# Modular_BO.net
KiCad netlist of a schematic drawn in Altium Designer
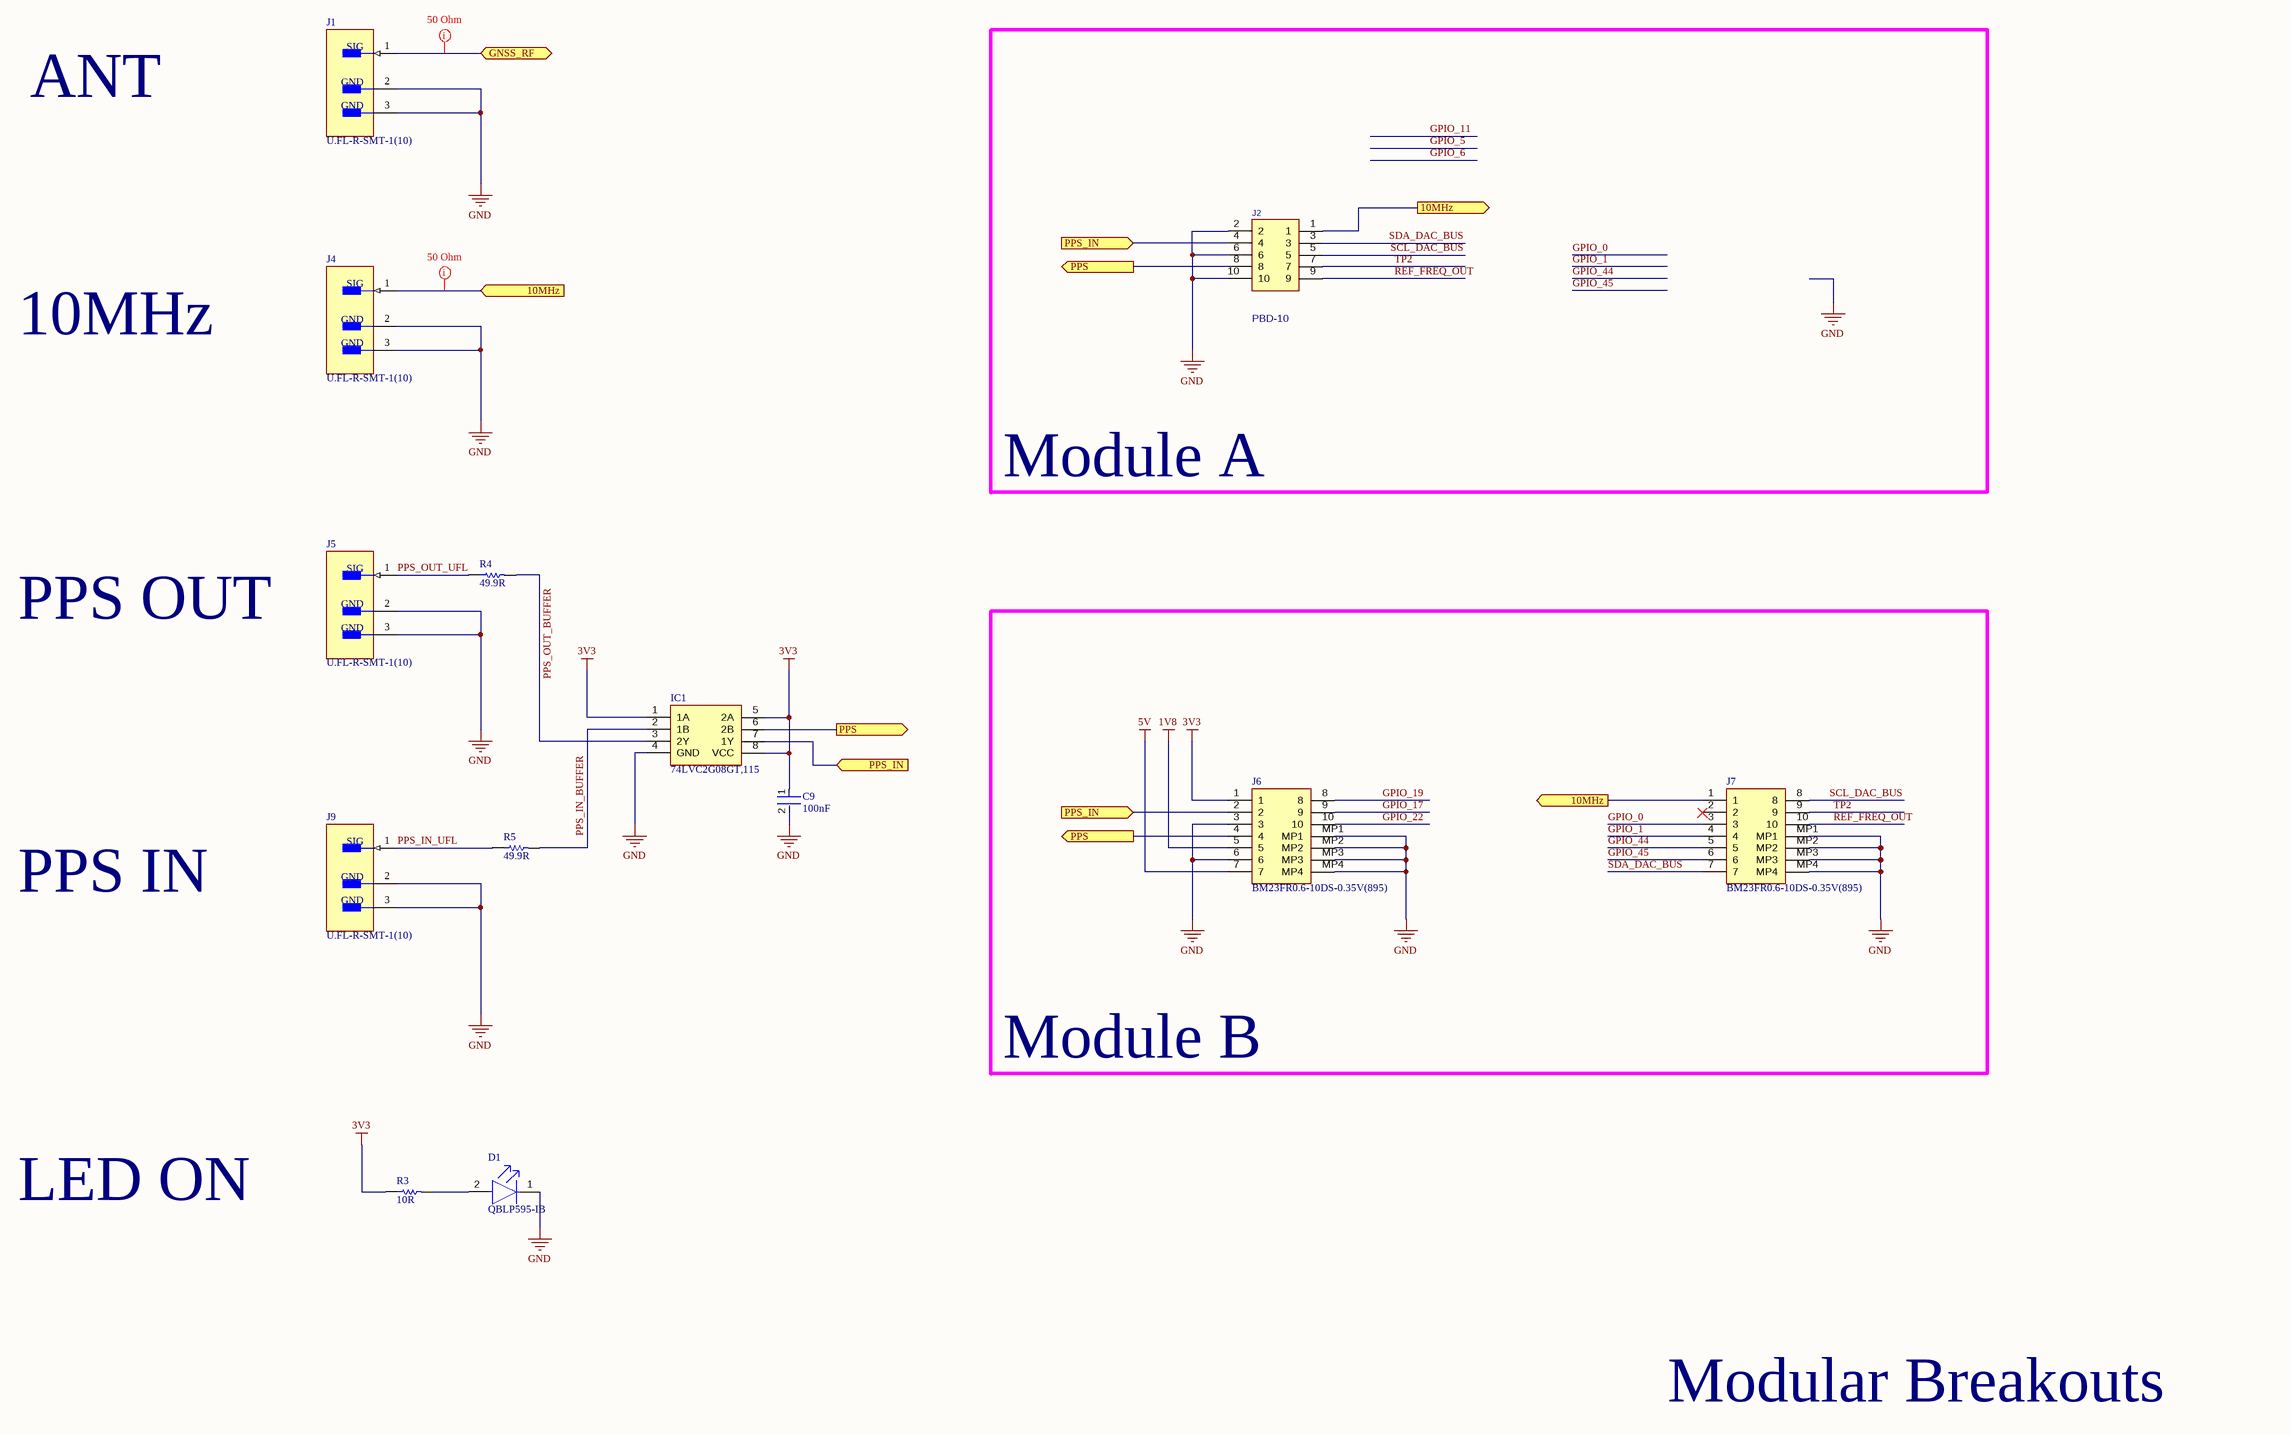
[diagram p0: Modular_BO.SchDoc]

(export (version "E")
  (design (tool "Eeschema 10.0.6"))
  (components
    (comp (ref "C9")
      (value "100nF")
      (footprint "FP-C0603C-CF-MFG")
      (description "CAP CER 0.1UF 50V 20% X7R 0603")
      (fields
        (field (name "MANUFACTURER PART NUMBER") "C0603C104M5RACTU")
        (field (name "MANUFACTURER") "KEMET")
      )
      (libsource (lib "Altium Content Vault") (part "b4654b650e69147ec39a6b967a45e02"))
    )
    (comp (ref "D1")
      (value "QBLP595-IB")
      (footprint "FP-QBLP595-IB-MFG")
      (description "LED BLUE CLEAR 0402 SMD")
      (libsource (lib "Altium Content Vault") (part "8706943c75ba83719d021d2fdc84c58"))
    )
    (comp (ref "IC1")
      (value "74LVC2G08GT,115")
      (footprint "SamacSys:74AVC9112GTX")
      (description "Integrated Circuit")
      (fields (field (name "MOUSER PART NUMBER") "771-LVC2G08GT115"))
      (libsource (lib "*") (part "74LVC2G08GT,115"))
    )
    (comp (ref "J1")
      (value "U.FL-R-SMT-1(10)")
      (footprint "FP-U_FL-R-SMT-1_10-MFG")
      (description "CONN U.FL RCPT STR 50 OHM SMD")
      (libsource (lib "Altium Content Vault") (part "7158abf7d987fa84906f6fb0d115710"))
    )
    (comp (ref "J2")
      (value "PBD-10")
      (footprint "PBD-10")
      (description "Connector")
      (fields (field (name "MANUFACTURER") "Connfly"))
      (libsource (lib "SamacSys") (part "PBD-10_1"))
    )
    (comp (ref "J4")
      (value "U.FL-R-SMT-1(10)")
      (footprint "FP-U_FL-R-SMT-1_10-MFG")
      (description "CONN U.FL RCPT STR 50 OHM SMD")
      (libsource (lib "Altium Content Vault") (part "7158abf7d987fa84906f6fb0d115710"))
    )
    (comp (ref "J5")
      (value "U.FL-R-SMT-1(10)")
      (footprint "FP-U_FL-R-SMT-1_10-MFG")
      (description "CONN U.FL RCPT STR 50 OHM SMD")
      (libsource (lib "Altium Content Vault") (part "7158abf7d987fa84906f6fb0d115710"))
    )
    (comp (ref "J6")
      (value "BM23FR0.6-10DS-0.35V(895)")
      (footprint "SamacSys:BM23FR0810DS035V895")
      (description "Connector")
      (fields
        (field (name "MANUFACTURER_PART_NUMBER") "BM23FR0.8-10DS-0.35V(895)")
        (field (name "MOUSER PART NUMBER") "798-3FR0810DS035V895")
      )
      (libsource (lib "*") (part "BM23FR0.8-10DS-0.35V_895_"))
    )
    (comp (ref "J7")
      (value "BM23FR0.6-10DS-0.35V(895)")
      (footprint "SamacSys:BM23FR0810DS035V895")
      (description "Connector")
      (fields
        (field (name "MANUFACTURER_PART_NUMBER") "BM23FR0.8-10DS-0.35V(895)")
        (field (name "MOUSER PART NUMBER") "798-3FR0810DS035V895")
      )
      (libsource (lib "*") (part "BM23FR0.8-10DS-0.35V_895_"))
    )
    (comp (ref "J9")
      (value "U.FL-R-SMT-1(10)")
      (footprint "FP-U_FL-R-SMT-1_10-MFG")
      (description "CONN U.FL RCPT STR 50 OHM SMD")
      (libsource (lib "Altium Content Vault") (part "7158abf7d987fa84906f6fb0d115710"))
    )
    (comp (ref "R3")
      (value "10R")
      (footprint "RESC1005X40X25NL05T10")
      (fields (field (name "PART NUMBER") "CRCW040210R0FKEDHP") (field (name "MANUFACTURER") "Vishay Dale"))
      (libsource (lib "Altium Content Vault") (part "RES"))
    )
    (comp (ref "R4")
      (value "49.9R")
      (footprint "RESC1608X55X25NL10T15")
      (libsource (lib "Altium Content Vault") (part "RES-2"))
    )
    (comp (ref "R5")
      (value "49.9R")
      (footprint "RESC1608X55X25NL10T15")
      (libsource (lib "Altium Content Vault") (part "RES-2"))
    )
  )
  (nets
    (net (code "1") (name "/10MHz") (class "Default")
      (node (ref "J2") (pin "1") (pinfunction "1_1") (pintype "passive"))
      (node (ref "J4") (pin "1") (pinfunction "SIG_1") (pintype "input"))
      (node (ref "J7") (pin "1") (pinfunction "1_1") (pintype "passive"))
    )
    (net (code "2") (name "/GNSS_RF") (class "Default")
      (node (ref "J1") (pin "1") (pinfunction "SIG_1") (pintype "input"))
    )
    (net (code "3") (name "/GPIO_0") (class "Default")
      (node (ref "J7") (pin "3") (pinfunction "3_3") (pintype "passive"))
    )
    (net (code "4") (name "/GPIO_1") (class "Default")
      (node (ref "J7") (pin "4") (pinfunction "4_4") (pintype "passive"))
    )
    (net (code "8") (name "/GPIO_17") (class "Default")
      (node (ref "J6") (pin "9") (pinfunction "9_9") (pintype "passive"))
    )
    (net (code "9") (name "/GPIO_19") (class "Default")
      (node (ref "J6") (pin "8") (pinfunction "8_8") (pintype "passive"))
    )
    (net (code "10") (name "/GPIO_22") (class "Default")
      (node (ref "J6") (pin "10") (pinfunction "10_10") (pintype "passive"))
    )
    (net (code "11") (name "/GPIO_44") (class "Default")
      (node (ref "J7") (pin "5") (pinfunction "5_5") (pintype "passive"))
    )
    (net (code "12") (name "/GPIO_45") (class "Default")
      (node (ref "J7") (pin "6") (pinfunction "6_6") (pintype "passive"))
    )
    (net (code "13") (name "/PPS") (class "Default")
      (node (ref "IC1") (pin "6") (pinfunction "2B_6") (pintype "passive"))
      (node (ref "J2") (pin "8") (pinfunction "8_8") (pintype "passive"))
      (node (ref "J6") (pin "4") (pinfunction "4_4") (pintype "passive"))
    )
    (net (code "14") (name "/PPS_IN") (class "Default")
      (node (ref "IC1") (pin "7") (pinfunction "1Y_7") (pintype "passive"))
      (node (ref "J2") (pin "4") (pinfunction "4_4") (pintype "passive"))
      (node (ref "J6") (pin "2") (pinfunction "2_2") (pintype "passive"))
    )
    (net (code "15") (name "/PPS_IN_BUFFER") (class "Default")
      (node (ref "IC1") (pin "2") (pinfunction "1B_2") (pintype "passive"))
      (node (ref "R5") (pin "2") (pinfunction "2_2") (pintype "passive"))
    )
    (net (code "16") (name "/PPS_IN_UFL") (class "Default")
      (node (ref "J9") (pin "1") (pinfunction "SIG_1") (pintype "input"))
      (node (ref "R5") (pin "1") (pinfunction "1_1") (pintype "passive"))
    )
    (net (code "17") (name "/PPS_OUT_BUFFER") (class "Default")
      (node (ref "IC1") (pin "3") (pinfunction "2Y_3") (pintype "passive"))
      (node (ref "R4") (pin "2") (pinfunction "2_2") (pintype "passive"))
    )
    (net (code "18") (name "/PPS_OUT_UFL") (class "Default")
      (node (ref "J5") (pin "1") (pinfunction "SIG_1") (pintype "input"))
      (node (ref "R4") (pin "1") (pinfunction "1_1") (pintype "passive"))
    )
    (net (code "19") (name "/REF_FREQ_OUT") (class "Default")
      (node (ref "J2") (pin "9") (pinfunction "9_9") (pintype "passive"))
      (node (ref "J7") (pin "10") (pinfunction "10_10") (pintype "passive"))
    )
    (net (code "20") (name "/SCL_DAC_BUS") (class "Default")
      (node (ref "J2") (pin "5") (pinfunction "5_5") (pintype "passive"))
      (node (ref "J7") (pin "8") (pinfunction "8_8") (pintype "passive"))
    )
    (net (code "21") (name "/SDA_DAC_BUS") (class "Default")
      (node (ref "J2") (pin "3") (pinfunction "3_3") (pintype "passive"))
      (node (ref "J7") (pin "7") (pinfunction "7_7") (pintype "passive"))
    )
    (net (code "22") (name "/TP2") (class "Default")
      (node (ref "J2") (pin "7") (pinfunction "7_7") (pintype "passive"))
      (node (ref "J7") (pin "9") (pinfunction "9_9") (pintype "passive"))
    )
    (net (code "23") (name "1V8") (class "Default")
      (node (ref "J6") (pin "5") (pinfunction "5_5") (pintype "passive"))
    )
    (net (code "24") (name "3V3") (class "Default")
      (node (ref "C9") (pin "1") (pinfunction "1_1") (pintype "passive"))
      (node (ref "IC1") (pin "1") (pinfunction "1A_1") (pintype "passive"))
      (node (ref "IC1") (pin "5") (pinfunction "2A_5") (pintype "passive"))
      (node (ref "IC1") (pin "8") (pinfunction "VCC_8") (pintype "passive"))
      (node (ref "J6") (pin "1") (pinfunction "1_1") (pintype "passive"))
      (node (ref "R3") (pin "1") (pinfunction "1_1") (pintype "passive"))
    )
    (net (code "25") (name "5V") (class "Default")
      (node (ref "J6") (pin "7") (pinfunction "7_7") (pintype "passive"))
    )
    (net (code "26") (name "GND") (class "Default")
      (node (ref "C9") (pin "2") (pinfunction "2_2") (pintype "passive"))
      (node (ref "D1") (pin "1") (pinfunction "C_1") (pintype "passive"))
      (node (ref "IC1") (pin "4") (pinfunction "GND_4") (pintype "passive"))
      (node (ref "J1") (pin "2") (pinfunction "GND_2") (pintype "power_in"))
      (node (ref "J1") (pin "3") (pinfunction "GND_3") (pintype "power_in"))
      (node (ref "J2") (pin "10") (pinfunction "10_10") (pintype "passive"))
      (node (ref "J2") (pin "2") (pinfunction "2_2") (pintype "passive"))
      (node (ref "J2") (pin "6") (pinfunction "6_6") (pintype "passive"))
      (node (ref "J4") (pin "2") (pinfunction "GND_2") (pintype "power_in"))
      (node (ref "J4") (pin "3") (pinfunction "GND_3") (pintype "power_in"))
      (node (ref "J5") (pin "2") (pinfunction "GND_2") (pintype "power_in"))
      (node (ref "J5") (pin "3") (pinfunction "GND_3") (pintype "power_in"))
      (node (ref "J6") (pin "3") (pinfunction "3_3") (pintype "passive"))
      (node (ref "J6") (pin "6") (pinfunction "6_6") (pintype "passive"))
      (node (ref "J6") (pin "MP1") (pinfunction "MP1_MP1") (pintype "passive"))
      (node (ref "J6") (pin "MP2") (pinfunction "MP2_MP2") (pintype "passive"))
      (node (ref "J6") (pin "MP3") (pinfunction "MP3_MP3") (pintype "passive"))
      (node (ref "J6") (pin "MP4") (pinfunction "MP4_MP4") (pintype "passive"))
      (node (ref "J7") (pin "MP1") (pinfunction "MP1_MP1") (pintype "passive"))
      (node (ref "J7") (pin "MP2") (pinfunction "MP2_MP2") (pintype "passive"))
      (node (ref "J7") (pin "MP3") (pinfunction "MP3_MP3") (pintype "passive"))
      (node (ref "J7") (pin "MP4") (pinfunction "MP4_MP4") (pintype "passive"))
      (node (ref "J9") (pin "2") (pinfunction "GND_2") (pintype "power_in"))
      (node (ref "J9") (pin "3") (pinfunction "GND_3") (pintype "power_in"))
    )
    (net (code "27") (name "Net-(D1-A)") (class "Default")
      (node (ref "D1") (pin "2") (pinfunction "A_2") (pintype "passive"))
      (node (ref "R3") (pin "2") (pinfunction "2_2") (pintype "passive"))
    )
    (net (code "28") (name "unconnected-(J7-Pad2)") (class "Default")
      (node (ref "J7") (pin "2") (pinfunction "2_2") (pintype "passive+no_connect"))
    )
  )
)
